# sd_card.net
KiCad netlist of a schematic drawn in Altium Designer
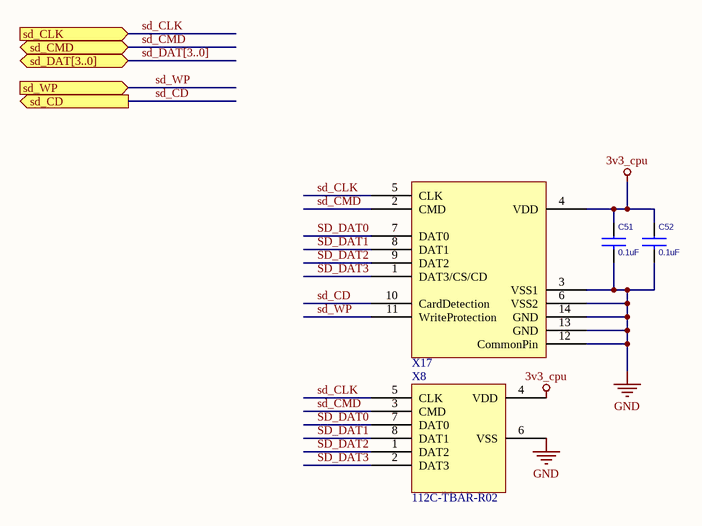
[diagram p0: sd_card.SchDoc]

(export (version "E")
  (design (tool "Eeschema 10.0.6"))
  (components
    (comp (ref "C51")
      (value "0.1uF")
      (footprint "CAPC2012X09M")
      (description "CAP CER 0.1UF 25V 10% X7R 0805")
      (libsource (lib "Capacitors") (part "CAP_SMD_0.1UF_10%"))
    )
    (comp (ref "C52")
      (value "0.1uF")
      (footprint "CAPC2012X09M")
      (description "CAP CER 0.1UF 25V 10% X7R 0805")
      (libsource (lib "Capacitors") (part "CAP_SMD_0.1UF_10%"))
    )
    (comp (ref "X8")
      (value "112C-TBAR-R02")
      (footprint "112C-TBAR-R02")
      (libsource (lib "Connectors") (part "112C-TBAR-R02"))
    )
    (comp (ref "X17")
      (value "104H-TDA0-R01")
      (footprint "104H-TDA0-R01")
      (libsource (lib "Connectors") (part "104H-TDA0-R01"))
    )
  )
  (nets
    (net (code "5") (name "/SD_DAT0") (class "Default")
      (node (ref "X17") (pin "7") (pinfunction "DAT0_7") (pintype "power_in"))
      (node (ref "X8") (pin "7") (pinfunction "DAT0_7") (pintype "passive"))
    )
    (net (code "6") (name "/SD_DAT1") (class "Default")
      (node (ref "X17") (pin "8") (pinfunction "DAT1_8") (pintype "power_in"))
      (node (ref "X8") (pin "8") (pinfunction "DAT1_8") (pintype "passive"))
    )
    (net (code "7") (name "/SD_DAT2") (class "Default")
      (node (ref "X17") (pin "9") (pinfunction "DAT2_9") (pintype "power_in"))
      (node (ref "X8") (pin "1") (pinfunction "DAT2_1") (pintype "passive"))
    )
    (net (code "8") (name "/SD_DAT3") (class "Default")
      (node (ref "X17") (pin "1") (pinfunction "DAT3/CS/CD_1") (pintype "power_in"))
      (node (ref "X8") (pin "2") (pinfunction "DAT3_2") (pintype "passive"))
    )
    (net (code "9") (name "/sd_CD") (class "Default")
      (node (ref "X17") (pin "10") (pinfunction "CardDetection_10") (pintype "power_in"))
    )
    (net (code "10") (name "/sd_CLK") (class "Default")
      (node (ref "X17") (pin "5") (pinfunction "CLK_5") (pintype "power_in"))
      (node (ref "X8") (pin "5") (pinfunction "CLK_5") (pintype "passive"))
    )
    (net (code "11") (name "/sd_CMD") (class "Default")
      (node (ref "X17") (pin "2") (pinfunction "CMD_2") (pintype "power_in"))
      (node (ref "X8") (pin "3") (pinfunction "CMD_3") (pintype "passive"))
    )
    (net (code "13") (name "/sd_WP") (class "Default")
      (node (ref "X17") (pin "11") (pinfunction "WriteProtection_11") (pintype "power_in"))
    )
    (net (code "14") (name "3v3_cpu") (class "Default")
      (node (ref "C51") (pin "1") (pinfunction "1_1") (pintype "passive"))
      (node (ref "C52") (pin "1") (pinfunction "1_1") (pintype "passive"))
      (node (ref "X17") (pin "4") (pinfunction "VDD_4") (pintype "power_in"))
      (node (ref "X8") (pin "4") (pinfunction "VDD_4") (pintype "passive"))
    )
    (net (code "15") (name "GND") (class "Default")
      (node (ref "C51") (pin "2") (pinfunction "2_2") (pintype "passive"))
      (node (ref "C52") (pin "2") (pinfunction "2_2") (pintype "passive"))
      (node (ref "X17") (pin "12") (pinfunction "CommonPin_12") (pintype "power_in"))
      (node (ref "X17") (pin "13") (pinfunction "GND_13") (pintype "power_in"))
      (node (ref "X17") (pin "14") (pinfunction "GND_14") (pintype "power_in"))
      (node (ref "X17") (pin "3") (pinfunction "VSS1_3") (pintype "power_in"))
      (node (ref "X17") (pin "6") (pinfunction "VSS2_6") (pintype "power_in"))
      (node (ref "X8") (pin "6") (pinfunction "VSS_6") (pintype "passive"))
    )
  )
)
